# rf_conn.net
KiCad netlist of a schematic drawn in Altium Designer
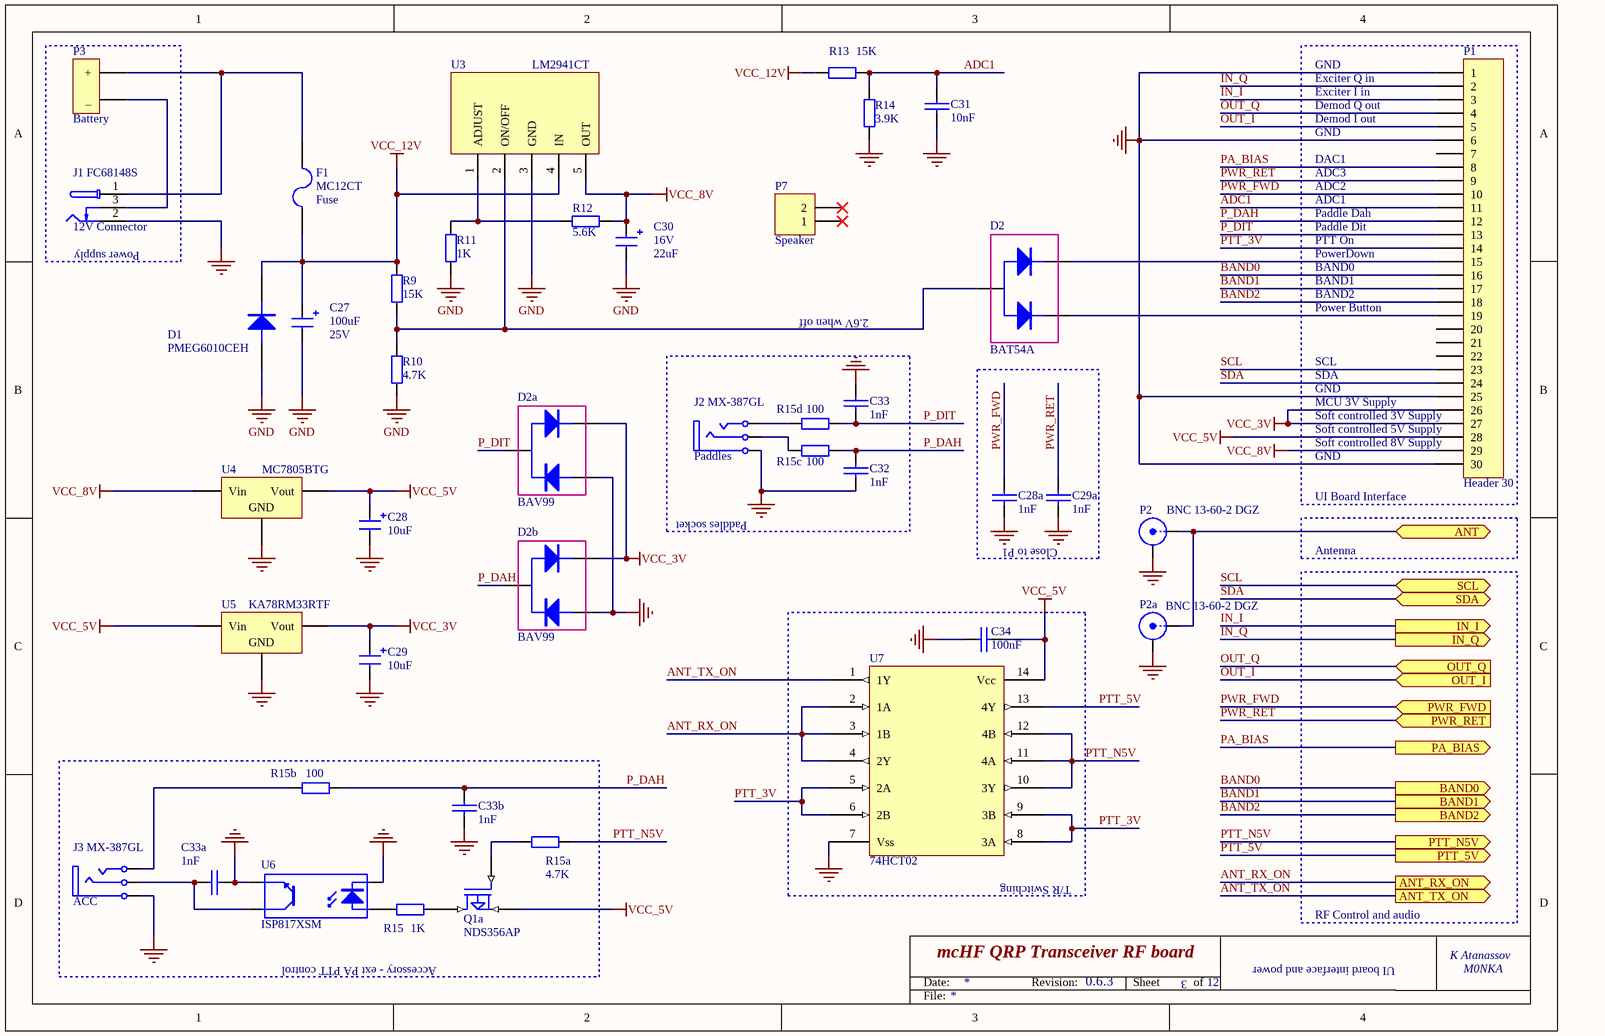
[diagram p0: rf_conn.SchDoc]

(export (version "E")
  (design (tool "Eeschema 10.0.6"))
  (components
    (comp (ref "C27")
      (value "100uF")
      (footprint "CAP_ALUM_1")
      (description "Electrolitic capacitor")
      (fields (field (name "VOLTAGE") "25V"))
      (libsource (lib "mcHF_rf") (part "CAP-POL"))
    )
    (comp (ref "C28")
      (value "10uF")
      (footprint "1206_Elec_Cap_N")
      (description "Electrolitic capacitor")
      (libsource (lib "mcHF_rf") (part "CAP-POL"))
    )
    (comp (ref "C28a")
      (value "1nF")
      (footprint "0805-Pro")
      (description "Capacitor")
      (libsource (lib "mcHF_rf") (part "CAP"))
    )
    (comp (ref "C29")
      (value "10uF")
      (footprint "1206_Elec_Cap_N")
      (description "Electrolitic capacitor")
      (libsource (lib "mcHF_rf") (part "CAP-POL"))
    )
    (comp (ref "C29a")
      (value "1nF")
      (footprint "0805-Pro")
      (description "Capacitor")
      (libsource (lib "mcHF_rf") (part "CAP"))
    )
    (comp (ref "C30")
      (value "22uF")
      (footprint "1206_Elec_Cap_N")
      (description "Electrolitic capacitor")
      (fields (field (name "VOLTAGE") "16V"))
      (libsource (lib "mcHF_rf") (part "CAP-POL"))
    )
    (comp (ref "C31")
      (value "10nF")
      (footprint "0805-Pro")
      (description "Capacitor")
      (libsource (lib "mcHF_rf") (part "CAP"))
    )
    (comp (ref "C32")
      (value "1nF")
      (footprint "0805-Pro")
      (description "Capacitor")
      (libsource (lib "mcHF_rf") (part "CAP"))
    )
    (comp (ref "C33")
      (value "1nF")
      (footprint "0805-Pro")
      (description "Capacitor")
      (libsource (lib "mcHF_rf") (part "CAP"))
    )
    (comp (ref "C33a")
      (value "1nF")
      (footprint "0805-Pro")
      (description "Capacitor")
      (libsource (lib "mcHF_rf") (part "CAP"))
    )
    (comp (ref "C33b")
      (value "1nF")
      (footprint "0805-Pro")
      (description "Capacitor")
      (libsource (lib "mcHF_rf") (part "CAP"))
    )
    (comp (ref "C34")
      (value "100nF")
      (footprint "0805-Pro")
      (description "Capacitor")
      (libsource (lib "mcHF_rf") (part "CAP"))
    )
    (comp (ref "D1")
      (value "PMEG6010CEH")
      (footprint "SOD87")
      (description "DIODE, SCHOTTKY, 1A, 60V, SOD-123F")
      (libsource (lib "mcHF_rf") (part "PMEG6010CEH"))
    )
    (comp (ref "D2")
      (value "BAT54A")
      (footprint "SOT-23")
      (description "DIODE, SCHOTTKY, DUAL")
      (libsource (lib "mcHF_rf") (part "BAT54A"))
    )
    (comp (ref "D2a")
      (value "BAV99")
      (footprint "SOT-23")
      (description "Small Signal Diode, Dual Series")
      (libsource (lib "mcHF_rf") (part "BAV99"))
    )
    (comp (ref "D2b")
      (value "BAV99")
      (footprint "SOT-23")
      (description "Small Signal Diode, Dual Series")
      (libsource (lib "mcHF_rf") (part "BAV99"))
    )
    (comp (ref "F1")
      (value "MC12CT")
      (footprint "1206")
      (description "Fuse")
      (fields (field (name "FUNCTION") "Fuse"))
      (libsource (lib "mcHF_rf") (part "Fuse"))
    )
    (comp (ref "J1")
      (value "FC68148S")
      (footprint "PowerJack")
      (description "Power Jack")
      (fields (field (name "FUNCTION") "12V Connector"))
      (libsource (lib "mcHF_rf") (part "POWER_JACK"))
    )
    (comp (ref "J2")
      (value "MX-387GL")
      (footprint "MX-387GL_new1")
      (description "Jack Socket,Thru-Hole")
      (fields (field (name "FUNCTION") "Paddles"))
      (libsource (lib "mcHF_rf") (part "Phonejack3"))
    )
    (comp (ref "J3")
      (value "MX-387GL")
      (footprint "MX-387GL_new1")
      (description "Jack Socket,Thru-Hole")
      (fields (field (name "FUNCTION") "ACC"))
      (libsource (lib "mcHF_rf") (part "Phonejack3"))
    )
    (comp (ref "P1")
      (value "Header 30")
      (footprint "HDR1X30")
      (description "Header, 30-Pin")
      (libsource (lib "mcHF_rf") (part "Header 30"))
    )
    (comp (ref "P2")
      (value "BNC 13-60-2 DGZ")
      (footprint "CON-SMA-RA-A")
      (description "RF COAXIAL, BNC, JACK")
      (libsource (lib "mcHF_rf") (part "BNC"))
    )
    (comp (ref "P2a")
      (value "BNC 13-60-2 DGZ")
      (footprint "BNC_RA CON")
      (description "RF COAXIAL, BNC, JACK")
      (libsource (lib "mcHF_rf") (part "BNC"))
    )
    (comp (ref "P3")
      (value "Battery")
      (footprint "BatteryTerminal")
      (description "Battery Terminal")
      (libsource (lib "mcHF_rf") (part "Battery"))
    )
    (comp (ref "P7")
      (value "Speaker")
      (footprint "SIP2")
      (description "Header, 2-Pin")
      (fields (field (name "CHECKED") "NA"))
      (libsource (lib "mcHF_ui") (part "Header 2"))
    )
    (comp (ref "Q1a")
      (value "NDS356AP")
      (footprint "SOT-23-Pro")
      (libsource (lib "mcHF_rf") (part "NDS356AP"))
    )
    (comp (ref "R9")
      (value "15K")
      (footprint "0805-Pro")
      (description "Resistor")
      (libsource (lib "mcHF_rf") (part "RES"))
    )
    (comp (ref "R10")
      (value "4.7K")
      (footprint "0805-Pro")
      (description "Resistor")
      (libsource (lib "") (part "RES_1"))
    )
    (comp (ref "R11")
      (value "1K")
      (footprint "0805-Pro")
      (description "Resistor")
      (libsource (lib "mcHF_rf") (part "RES"))
    )
    (comp (ref "R12")
      (value "5.6K")
      (footprint "0805-Pro")
      (description "Resistor")
      (libsource (lib "") (part "RES_2"))
    )
    (comp (ref "R13")
      (value "15K")
      (footprint "0805-Pro")
      (description "Resistor")
      (libsource (lib "") (part "RES_2"))
    )
    (comp (ref "R14")
      (value "3.9K")
      (footprint "0805-Pro")
      (description "Resistor")
      (libsource (lib "") (part "RES_1"))
    )
    (comp (ref "R15")
      (value "1K")
      (footprint "0805-Pro")
      (description "Resistor")
      (libsource (lib "") (part "RES_2"))
    )
    (comp (ref "R15a")
      (value "4.7K")
      (footprint "0805-Pro")
      (description "Resistor")
      (libsource (lib "") (part "RES_2"))
    )
    (comp (ref "R15b")
      (value "100")
      (footprint "0805-Pro")
      (description "Resistor")
      (libsource (lib "*") (part "RES"))
    )
    (comp (ref "R15c")
      (value "100")
      (footprint "0805-Pro")
      (description "Resistor")
      (libsource (lib "*") (part "RES"))
    )
    (comp (ref "R15d")
      (value "100")
      (footprint "0805-Pro")
      (description "Resistor")
      (libsource (lib "*") (part "RES"))
    )
    (comp (ref "U3")
      (value "LM2941CT")
      (footprint "TO-220-5")
      (description "V REG ADJ +5/20V, 2941, TO-220-5")
      (libsource (lib "mcHF_rf") (part "LM2941CT"))
    )
    (comp (ref "U4")
      (value "MC7805BTG")
      (footprint "TO-220")
      (description "VOLTAGE REG, 40V, TO220-3")
      (libsource (lib "mcHF_rf") (part "MC7805BTG"))
    )
    (comp (ref "U5")
      (value "KA78RM33RTF")
      (footprint "TO-252")
      (description "VOLT REG, 3.3V, TO-252")
      (libsource (lib "mcHF_rf") (part "UA78M33CKVURG3"))
    )
    (comp (ref "U6")
      (value "ISP817XSM")
      (footprint "SMDIP-4_new1")
      (description "OPTOCOUPLER, SMDIP-4, TR O/P")
      (libsource (lib "mcHF_rf") (part "ISP817XSM"))
    )
    (comp (ref "U7")
      (value "74HCT02")
      (footprint "SO-14-Pro")
      (description "Quad 2-input NOR gate")
      (libsource (lib "mcHF_rf") (part "74HCT02"))
    )
  )
  (nets
    (net (code "1") (name "/ADC1") (class "Default")
      (node (ref "C31") (pin "1") (pinfunction "1_1") (pintype "passive"))
      (node (ref "P1") (pin "11") (pinfunction "11_11") (pintype "passive"))
      (node (ref "R13") (pin "2") (pinfunction "2_2") (pintype "passive"))
      (node (ref "R14") (pin "1") (pinfunction "1_1") (pintype "passive"))
    )
    (net (code "2") (name "/ANT") (class "Default")
      (node (ref "P2") (pin "1") (pinfunction "X_1") (pintype "passive"))
      (node (ref "P2a") (pin "1") (pinfunction "X_1") (pintype "passive"))
    )
    (net (code "3") (name "/ANT_RX_ON") (class "Default")
      (node (ref "U7") (pin "2") (pinfunction "1A_2") (pintype "input"))
      (node (ref "U7") (pin "3") (pinfunction "1B_3") (pintype "input"))
      (node (ref "U7") (pin "4") (pinfunction "2Y_4") (pintype "output"))
    )
    (net (code "4") (name "/ANT_TX_ON") (class "Default")
      (node (ref "U7") (pin "1") (pinfunction "1Y_1") (pintype "output"))
    )
    (net (code "5") (name "/BAND0") (class "Default")
      (node (ref "P1") (pin "16") (pinfunction "16_16") (pintype "passive"))
    )
    (net (code "6") (name "/BAND1") (class "Default")
      (node (ref "P1") (pin "17") (pinfunction "17_17") (pintype "passive"))
    )
    (net (code "7") (name "/BAND2") (class "Default")
      (node (ref "P1") (pin "18") (pinfunction "18_18") (pintype "passive"))
    )
    (net (code "8") (name "/IN_I") (class "Default")
      (node (ref "P1") (pin "3") (pinfunction "3_3") (pintype "passive"))
    )
    (net (code "9") (name "/IN_Q") (class "Default")
      (node (ref "P1") (pin "2") (pinfunction "2_2") (pintype "passive"))
    )
    (net (code "10") (name "/OUT_I") (class "Default")
      (node (ref "P1") (pin "5") (pinfunction "5_5") (pintype "passive"))
    )
    (net (code "11") (name "/OUT_Q") (class "Default")
      (node (ref "P1") (pin "4") (pinfunction "4_4") (pintype "passive"))
    )
    (net (code "12") (name "/PA_BIAS") (class "Default")
      (node (ref "P1") (pin "8") (pinfunction "8_8") (pintype "passive"))
    )
    (net (code "13") (name "/PTT_3V") (class "Default")
      (node (ref "P1") (pin "14") (pinfunction "14_14") (pintype "passive"))
      (node (ref "U7") (pin "5") (pinfunction "2A_5") (pintype "input"))
      (node (ref "U7") (pin "6") (pinfunction "2B_6") (pintype "input"))
      (node (ref "U7") (pin "8") (pinfunction "3A_8") (pintype "input"))
      (node (ref "U7") (pin "9") (pinfunction "3B_9") (pintype "input"))
    )
    (net (code "14") (name "/PTT_5V") (class "Default")
      (node (ref "U7") (pin "13") (pinfunction "4Y_13") (pintype "output"))
    )
    (net (code "15") (name "/PTT_N5V") (class "Default")
      (node (ref "R15a") (pin "2") (pinfunction "2_2") (pintype "passive"))
      (node (ref "U7") (pin "10") (pinfunction "3Y_10") (pintype "output"))
      (node (ref "U7") (pin "11") (pinfunction "4A_11") (pintype "input"))
      (node (ref "U7") (pin "12") (pinfunction "4B_12") (pintype "input"))
    )
    (net (code "16") (name "/PWR_FWD") (class "Default")
      (node (ref "C28a") (pin "2") (pinfunction "2_2") (pintype "passive"))
      (node (ref "P1") (pin "10") (pinfunction "10_10") (pintype "passive"))
    )
    (net (code "17") (name "/PWR_RET") (class "Default")
      (node (ref "C29a") (pin "2") (pinfunction "2_2") (pintype "passive"))
      (node (ref "P1") (pin "9") (pinfunction "9_9") (pintype "passive"))
    )
    (net (code "18") (name "/P_DAH") (class "Default")
      (node (ref "C32") (pin "2") (pinfunction "2_2") (pintype "passive"))
      (node (ref "C33b") (pin "1") (pinfunction "1_1") (pintype "passive"))
      (node (ref "D2b") (pin "3") (pinfunction "C_3") (pintype "passive"))
      (node (ref "P1") (pin "12") (pinfunction "12_12") (pintype "passive"))
      (node (ref "R15b") (pin "1") (pinfunction "1_1") (pintype "passive"))
      (node (ref "R15c") (pin "1") (pinfunction "1_1") (pintype "passive"))
    )
    (net (code "19") (name "/P_DIT") (class "Default")
      (node (ref "C33") (pin "1") (pinfunction "1_1") (pintype "passive"))
      (node (ref "D2a") (pin "3") (pinfunction "C_3") (pintype "passive"))
      (node (ref "P1") (pin "13") (pinfunction "13_13") (pintype "passive"))
      (node (ref "R15d") (pin "1") (pinfunction "1_1") (pintype "passive"))
    )
    (net (code "20") (name "/SCL") (class "Default")
      (node (ref "P1") (pin "23") (pinfunction "23_23") (pintype "passive"))
    )
    (net (code "21") (name "/SDA") (class "Default")
      (node (ref "P1") (pin "24") (pinfunction "24_24") (pintype "passive"))
    )
    (net (code "22") (name "GND") (class "Default")
      (node (ref "C27") (pin "2") (pinfunction "2_2") (pintype "passive"))
      (node (ref "C28") (pin "2") (pinfunction "2_2") (pintype "passive"))
      (node (ref "C28a") (pin "1") (pinfunction "1_1") (pintype "passive"))
      (node (ref "C29") (pin "2") (pinfunction "2_2") (pintype "passive"))
      (node (ref "C29a") (pin "1") (pinfunction "1_1") (pintype "passive"))
      (node (ref "C30") (pin "2") (pinfunction "2_2") (pintype "passive"))
      (node (ref "C31") (pin "2") (pinfunction "2_2") (pintype "passive"))
      (node (ref "C32") (pin "1") (pinfunction "1_1") (pintype "passive"))
      (node (ref "C33") (pin "2") (pinfunction "2_2") (pintype "passive"))
      (node (ref "C33a") (pin "1") (pinfunction "1_1") (pintype "passive"))
      (node (ref "C33b") (pin "2") (pinfunction "2_2") (pintype "passive"))
      (node (ref "C34") (pin "2") (pinfunction "2_2") (pintype "passive"))
      (node (ref "D1") (pin "1") (pinfunction "A_1") (pintype "passive"))
      (node (ref "D2a") (pin "1") (pinfunction "A1_1") (pintype "passive"))
      (node (ref "D2b") (pin "1") (pinfunction "A1_1") (pintype "passive"))
      (node (ref "J1") (pin "2") (pintype "passive"))
      (node (ref "J2") (pin "S") (pinfunction "S_S") (pintype "power_in"))
      (node (ref "J3") (pin "S") (pinfunction "S_S") (pintype "power_in"))
      (node (ref "P1") (pin "1") (pinfunction "1_1") (pintype "passive"))
      (node (ref "P1") (pin "25") (pinfunction "25_25") (pintype "passive"))
      (node (ref "P1") (pin "30") (pinfunction "30_30") (pintype "passive"))
      (node (ref "P1") (pin "6") (pinfunction "6_6") (pintype "passive"))
      (node (ref "P2") (pin "2") (pinfunction "Y_2") (pintype "passive"))
      (node (ref "P2a") (pin "2") (pinfunction "Y_2") (pintype "passive"))
      (node (ref "R10") (pin "2") (pinfunction "2_2") (pintype "passive"))
      (node (ref "R11") (pin "1") (pinfunction "1_1") (pintype "passive"))
      (node (ref "R14") (pin "2") (pinfunction "2_2") (pintype "passive"))
      (node (ref "U3") (pin "3") (pinfunction "GND_3") (pintype "passive"))
      (node (ref "U4") (pin "2") (pinfunction "GND_2") (pintype "passive"))
      (node (ref "U5") (pin "2") (pinfunction "GND_2") (pintype "passive"))
      (node (ref "U6") (pin "2") (pinfunction "K_2") (pintype "passive"))
      (node (ref "U6") (pin "3") (pinfunction "E_3") (pintype "passive"))
      (node (ref "U7") (pin "7") (pinfunction "Vss_7") (pintype "power_in"))
    )
    (net (code "23") (name "Net-(D2-A)") (class "Default")
      (node (ref "D2") (pin "3") (pinfunction "A_3") (pintype "passive"))
      (node (ref "R10") (pin "1") (pinfunction "1_1") (pintype "passive"))
      (node (ref "R9") (pin "1") (pinfunction "1_1") (pintype "passive"))
      (node (ref "U3") (pin "2") (pinfunction "ON/OFF_2") (pintype "passive"))
    )
    (net (code "24") (name "Net-(D2-K1)") (class "Default")
      (node (ref "D2") (pin "1") (pinfunction "K1_1") (pintype "passive"))
      (node (ref "P1") (pin "19") (pinfunction "19_19") (pintype "passive"))
    )
    (net (code "25") (name "Net-(D2-K2)") (class "Default")
      (node (ref "D2") (pin "2") (pinfunction "K2_2") (pintype "passive"))
      (node (ref "P1") (pin "15") (pinfunction "15_15") (pintype "passive"))
    )
    (net (code "26") (name "Net-(J2-PadR)") (class "Default")
      (node (ref "J2") (pin "R") (pinfunction "R_R") (pintype "passive"))
      (node (ref "R15c") (pin "2") (pinfunction "2_2") (pintype "passive"))
    )
    (net (code "27") (name "Net-(J2-PadT)") (class "Default")
      (node (ref "J2") (pin "T") (pinfunction "T_T") (pintype "passive"))
      (node (ref "R15d") (pin "2") (pinfunction "2_2") (pintype "passive"))
    )
    (net (code "28") (name "Net-(J3-PadT)") (class "Default")
      (node (ref "J3") (pin "T") (pinfunction "T_T") (pintype "passive"))
      (node (ref "R15b") (pin "2") (pinfunction "2_2") (pintype "passive"))
    )
    (net (code "29") (name "Net-(P3-+)") (class "Default")
      (node (ref "F1") (pin "2") (pinfunction "2_2") (pintype "passive"))
      (node (ref "J1") (pin "1") (pintype "passive"))
      (node (ref "P3") (pin "1") (pinfunction "+_1") (pintype "passive"))
    )
    (net (code "30") (name "Net-(P3-_)") (class "Default")
      (node (ref "J1") (pin "3") (pintype "passive"))
      (node (ref "P3") (pin "2") (pinfunction "__2") (pintype "passive"))
    )
    (net (code "31") (name "Net-(Q1a-D)") (class "Default")
      (node (ref "Q1a") (pin "3") (pinfunction "D_3") (pintype "input"))
      (node (ref "R15") (pin "2") (pinfunction "2_2") (pintype "passive"))
    )
    (net (code "32") (name "Net-(Q1a-G)") (class "Default")
      (node (ref "Q1a") (pin "1") (pinfunction "G_1") (pintype "input"))
      (node (ref "R15a") (pin "1") (pinfunction "1_1") (pintype "passive"))
    )
    (net (code "33") (name "Net-(U3-ADJUST)") (class "Default")
      (node (ref "R11") (pin "2") (pinfunction "2_2") (pintype "passive"))
      (node (ref "R12") (pin "1") (pinfunction "1_1") (pintype "passive"))
      (node (ref "U3") (pin "1") (pinfunction "ADJUST_1") (pintype "passive"))
    )
    (net (code "34") (name "Net-(U6-A)") (class "Default")
      (node (ref "R15") (pin "1") (pinfunction "1_1") (pintype "passive"))
      (node (ref "U6") (pin "1") (pinfunction "A_1") (pintype "passive"))
    )
    (net (code "35") (name "Net-(U6-C)") (class "Default")
      (node (ref "C33a") (pin "2") (pinfunction "2_2") (pintype "passive"))
      (node (ref "J3") (pin "R") (pinfunction "R_R") (pintype "passive"))
      (node (ref "U6") (pin "4") (pinfunction "C_4") (pintype "passive"))
    )
    (net (code "36") (name "VCC_3V") (class "Default")
      (node (ref "C29") (pin "1") (pinfunction "1_1") (pintype "passive"))
      (node (ref "D2a") (pin "2") (pinfunction "K1_2") (pintype "passive"))
      (node (ref "D2b") (pin "2") (pinfunction "K1_2") (pintype "passive"))
      (node (ref "P1") (pin "26") (pinfunction "26_26") (pintype "passive"))
      (node (ref "P1") (pin "27") (pinfunction "27_27") (pintype "passive"))
      (node (ref "U5") (pin "3") (pinfunction "Vout_3") (pintype "passive"))
    )
    (net (code "37") (name "VCC_5V") (class "Default")
      (node (ref "C28") (pin "1") (pinfunction "1_1") (pintype "passive"))
      (node (ref "C34") (pin "1") (pinfunction "1_1") (pintype "passive"))
      (node (ref "P1") (pin "28") (pinfunction "28_28") (pintype "passive"))
      (node (ref "Q1a") (pin "2") (pinfunction "S_2") (pintype "input"))
      (node (ref "U4") (pin "3") (pinfunction "Vout_3") (pintype "passive"))
      (node (ref "U5") (pin "1") (pinfunction "Vin_1") (pintype "passive"))
      (node (ref "U7") (pin "14") (pinfunction "Vcc_14") (pintype "power_in"))
    )
    (net (code "38") (name "VCC_8V") (class "Default")
      (node (ref "C30") (pin "1") (pinfunction "1_1") (pintype "passive"))
      (node (ref "P1") (pin "29") (pinfunction "29_29") (pintype "passive"))
      (node (ref "R12") (pin "2") (pinfunction "2_2") (pintype "passive"))
      (node (ref "U3") (pin "5") (pinfunction "OUT_5") (pintype "passive"))
      (node (ref "U4") (pin "1") (pinfunction "Vin_1") (pintype "passive"))
    )
    (net (code "39") (name "VCC_12V") (class "Default")
      (node (ref "C27") (pin "1") (pinfunction "1_1") (pintype "passive"))
      (node (ref "D1") (pin "2") (pinfunction "K_2") (pintype "passive"))
      (node (ref "F1") (pin "1") (pinfunction "1_1") (pintype "passive"))
      (node (ref "R13") (pin "1") (pinfunction "1_1") (pintype "passive"))
      (node (ref "R9") (pin "2") (pinfunction "2_2") (pintype "passive"))
      (node (ref "U3") (pin "4") (pinfunction "IN_4") (pintype "passive"))
    )
    (net (code "40") (name "unconnected-(P1-Pad7)") (class "Default")
      (node (ref "P1") (pin "7") (pinfunction "7_7") (pintype "passive"))
    )
    (net (code "41") (name "unconnected-(P1-Pad20)") (class "Default")
      (node (ref "P1") (pin "20") (pinfunction "20_20") (pintype "passive"))
    )
    (net (code "42") (name "unconnected-(P1-Pad21)") (class "Default")
      (node (ref "P1") (pin "21") (pinfunction "21_21") (pintype "passive"))
    )
    (net (code "43") (name "unconnected-(P1-Pad22)") (class "Default")
      (node (ref "P1") (pin "22") (pinfunction "22_22") (pintype "passive"))
    )
    (net (code "44") (name "unconnected-(P7-Pad1)") (class "Default")
      (node (ref "P7") (pin "1") (pinfunction "1_1") (pintype "passive+no_connect"))
    )
    (net (code "45") (name "unconnected-(P7-Pad2)") (class "Default")
      (node (ref "P7") (pin "2") (pinfunction "2_2") (pintype "passive+no_connect"))
    )
  )
)
